# tapeint.net
KiCad netlist of a schematic drawn in EAGLE
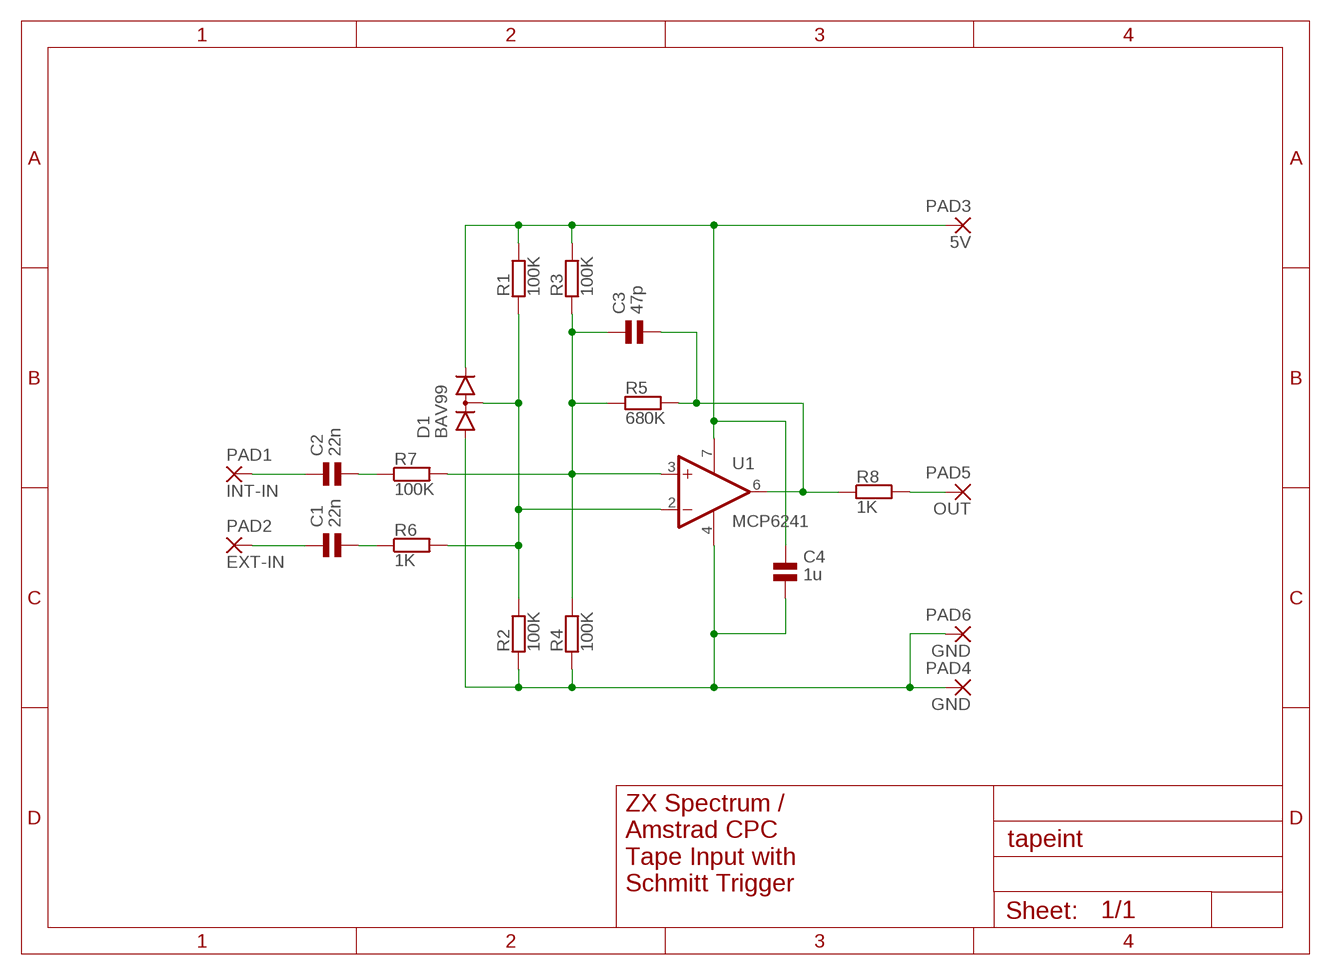
[diagram p0: schematic, sheet 1]

(export (version "E")
  (design (tool "Eeschema 10.0.6"))
  (components
    (comp (ref "C1")
      (value "22n")
      (footprint "eagle-import:0805")
      (libsource (lib "eagle-import") (part "CAP_NPOL0805-"))
    )
    (comp (ref "C2")
      (value "22n")
      (footprint "eagle-import:0805")
      (libsource (lib "eagle-import") (part "CAP_NPOL0805-"))
    )
    (comp (ref "C3")
      (value "47p")
      (footprint "eagle-import:0805")
      (libsource (lib "eagle-import") (part "CAP_NPOL0805-"))
    )
    (comp (ref "C4")
      (value "1u")
      (footprint "eagle-import:0805")
      (libsource (lib "eagle-import") (part "CAP_NPOL0805-"))
    )
    (comp (ref "D1")
      (value "BAV99")
      (footprint "eagle-import:SOT23")
      (libsource (lib "eagle-import") (part "BAV99"))
    )
    (comp (ref "PAD1")
      (value "INT-IN")
      (footprint "eagle-import:2,54_1,0")
      (libsource (lib "eagle-import") (part "WIREPAD2,54/1,0"))
    )
    (comp (ref "PAD2")
      (value "EXT-IN")
      (footprint "eagle-import:2,54_1,0")
      (libsource (lib "eagle-import") (part "WIREPAD2,54/1,0"))
    )
    (comp (ref "PAD3")
      (value "5V")
      (footprint "eagle-import:2,54_1,0")
      (libsource (lib "eagle-import") (part "WIREPAD2,54/1,0"))
    )
    (comp (ref "PAD4")
      (value "GND")
      (footprint "eagle-import:2,54_1,0")
      (libsource (lib "eagle-import") (part "WIREPAD2,54/1,0"))
    )
    (comp (ref "PAD5")
      (value "OUT")
      (footprint "eagle-import:2,54_1,0")
      (libsource (lib "eagle-import") (part "WIREPAD2,54/1,0"))
    )
    (comp (ref "PAD6")
      (value "GND")
      (footprint "eagle-import:2,54_1,0")
      (libsource (lib "eagle-import") (part "WIREPAD2,54/1,0"))
    )
    (comp (ref "R1")
      (value "100K")
      (footprint "eagle-import:0805")
      (libsource (lib "eagle-import") (part "RESSMD_0805-"))
    )
    (comp (ref "R2")
      (value "100K")
      (footprint "eagle-import:0805")
      (libsource (lib "eagle-import") (part "RESSMD_0805-"))
    )
    (comp (ref "R3")
      (value "100K")
      (footprint "eagle-import:0805")
      (libsource (lib "eagle-import") (part "RESSMD_0805-"))
    )
    (comp (ref "R4")
      (value "100K")
      (footprint "eagle-import:0805")
      (libsource (lib "eagle-import") (part "RESSMD_0805-"))
    )
    (comp (ref "R5")
      (value "680K")
      (footprint "eagle-import:0805")
      (libsource (lib "eagle-import") (part "RESSMD_0805-"))
    )
    (comp (ref "R6")
      (value "1K")
      (footprint "eagle-import:0805")
      (libsource (lib "eagle-import") (part "RESSMD_0805-"))
    )
    (comp (ref "R7")
      (value "100K")
      (footprint "eagle-import:0805")
      (libsource (lib "eagle-import") (part "RESSMD_0805-"))
    )
    (comp (ref "R8")
      (value "1K")
      (footprint "eagle-import:0805")
      (libsource (lib "eagle-import") (part "RESSMD_0805-"))
    )
    (comp (ref "U1")
      (value "MCP6241")
      (footprint "eagle-import:SO08")
      (libsource (lib "eagle-import") (part "1AMP_P7+4D"))
    )
  )
  (nets
    (net (code "1") (name "Net-(C1-Pad2)") (class "Default")
      (node (ref "C1") (pin "2") (pinfunction "2_2") (pintype "passive"))
      (node (ref "R6") (pin "1") (pinfunction "1_1") (pintype "passive"))
    )
    (net (code "2") (name "Net-(C2-Pad2)") (class "Default")
      (node (ref "C2") (pin "2") (pinfunction "2_2") (pintype "passive"))
      (node (ref "R7") (pin "1") (pinfunction "1_1") (pintype "passive"))
    )
    (net (code "3") (name "Net-(D1-A1)") (class "Default")
      (node (ref "C4") (pin "2") (pinfunction "2_2") (pintype "passive"))
      (node (ref "D1") (pin "1") (pinfunction "A1_1") (pintype "passive"))
      (node (ref "PAD4") (pin "1") (pinfunction "P_1") (pintype "passive"))
      (node (ref "PAD6") (pin "1") (pinfunction "P_1") (pintype "passive"))
      (node (ref "R2") (pin "1") (pinfunction "1_1") (pintype "passive"))
      (node (ref "R4") (pin "1") (pinfunction "1_1") (pintype "passive"))
      (node (ref "U1") (pin "4") (pinfunction "V-_4") (pintype "power_in"))
    )
    (net (code "4") (name "Net-(D1-K1A2)") (class "Default")
      (node (ref "D1") (pin "3") (pinfunction "K1A2_3") (pintype "passive"))
      (node (ref "R1") (pin "1") (pinfunction "1_1") (pintype "passive"))
      (node (ref "R2") (pin "2") (pinfunction "2_2") (pintype "passive"))
      (node (ref "R6") (pin "2") (pinfunction "2_2") (pintype "passive"))
      (node (ref "U1") (pin "2") (pinfunction "-IN_2") (pintype "input"))
    )
    (net (code "5") (name "Net-(D1-K2)") (class "Default")
      (node (ref "C4") (pin "1") (pinfunction "1_1") (pintype "passive"))
      (node (ref "D1") (pin "2") (pinfunction "K2_2") (pintype "passive"))
      (node (ref "PAD3") (pin "1") (pinfunction "P_1") (pintype "passive"))
      (node (ref "R1") (pin "2") (pinfunction "2_2") (pintype "passive"))
      (node (ref "R3") (pin "2") (pinfunction "2_2") (pintype "passive"))
      (node (ref "U1") (pin "7") (pinfunction "V+_7") (pintype "power_in"))
    )
    (net (code "6") (name "Net-(PAD1-P)") (class "Default")
      (node (ref "C2") (pin "1") (pinfunction "1_1") (pintype "passive"))
      (node (ref "PAD1") (pin "1") (pinfunction "P_1") (pintype "passive"))
    )
    (net (code "7") (name "Net-(PAD2-P)") (class "Default")
      (node (ref "C1") (pin "1") (pinfunction "1_1") (pintype "passive"))
      (node (ref "PAD2") (pin "1") (pinfunction "P_1") (pintype "passive"))
    )
    (net (code "8") (name "Net-(PAD5-P)") (class "Default")
      (node (ref "PAD5") (pin "1") (pinfunction "P_1") (pintype "passive"))
      (node (ref "R8") (pin "2") (pinfunction "2_2") (pintype "passive"))
    )
    (net (code "9") (name "Net-(U1-+IN)") (class "Default")
      (node (ref "C3") (pin "1") (pinfunction "1_1") (pintype "passive"))
      (node (ref "R3") (pin "1") (pinfunction "1_1") (pintype "passive"))
      (node (ref "R4") (pin "2") (pinfunction "2_2") (pintype "passive"))
      (node (ref "R5") (pin "1") (pinfunction "1_1") (pintype "passive"))
      (node (ref "R7") (pin "2") (pinfunction "2_2") (pintype "passive"))
      (node (ref "U1") (pin "3") (pinfunction "+IN_3") (pintype "input"))
    )
    (net (code "10") (name "Net-(U1-OUT)") (class "Default")
      (node (ref "C3") (pin "2") (pinfunction "2_2") (pintype "passive"))
      (node (ref "R5") (pin "2") (pinfunction "2_2") (pintype "passive"))
      (node (ref "R8") (pin "1") (pinfunction "1_1") (pintype "passive"))
      (node (ref "U1") (pin "6") (pinfunction "OUT_6") (pintype "output"))
    )
  )
)
